# coreless.net
KiCad netlist of a schematic drawn in EAGLE
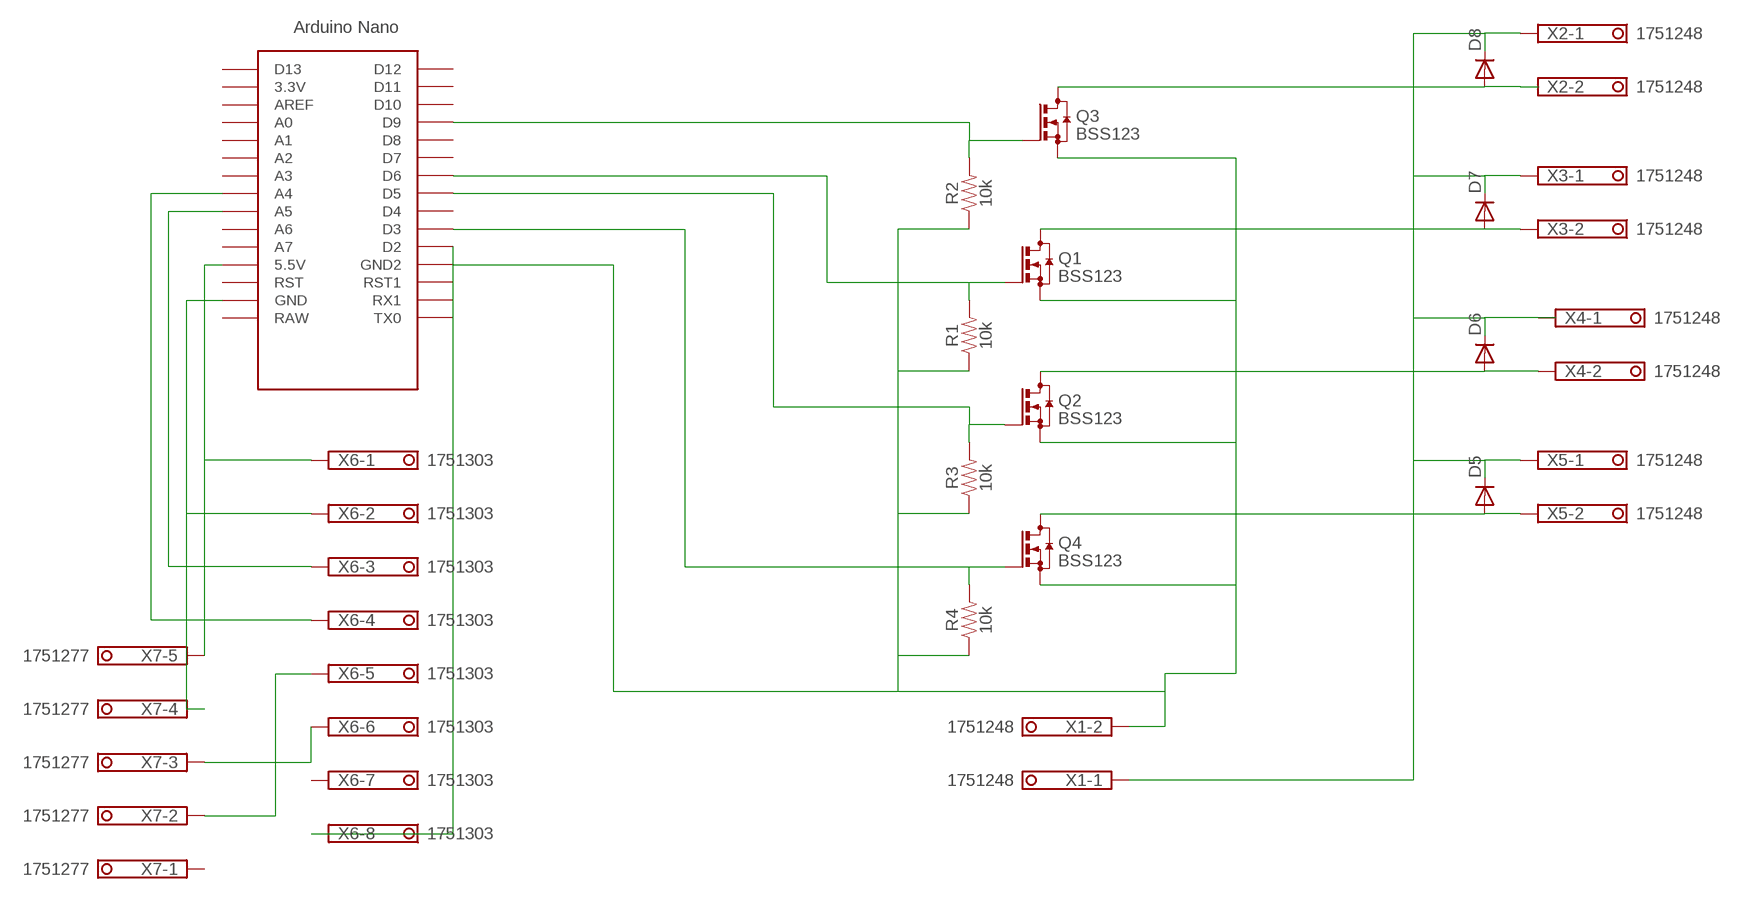
[diagram p0: schematic, sheet 1]

(export (version "E")
  (design (tool "Eeschema 10.0.6"))
  (components
    (comp (ref "D5")
      (value "DIODE-DO-214AC")
      (footprint "eagle-import:DO-214AC")
      (libsource (lib "eagle-import") (part "DIODE-DO-214AC"))
    )
    (comp (ref "D6")
      (value "DIODE-DO-214AC")
      (footprint "eagle-import:DO-214AC")
      (libsource (lib "eagle-import") (part "DIODE-DO-214AC"))
    )
    (comp (ref "D7")
      (value "DIODE-DO-214AC")
      (footprint "eagle-import:DO-214AC")
      (libsource (lib "eagle-import") (part "DIODE-DO-214AC"))
    )
    (comp (ref "D8")
      (value "DIODE-DO-214AC")
      (footprint "eagle-import:DO-214AC")
      (libsource (lib "eagle-import") (part "DIODE-DO-214AC"))
    )
    (comp (ref "Q1")
      (value "BSS123")
      (footprint "eagle-import:SOT23")
      (libsource (lib "eagle-import") (part "BSS123"))
    )
    (comp (ref "Q2")
      (value "BSS123")
      (footprint "eagle-import:SOT23")
      (libsource (lib "eagle-import") (part "BSS123"))
    )
    (comp (ref "Q3")
      (value "BSS123")
      (footprint "eagle-import:SOT23")
      (libsource (lib "eagle-import") (part "BSS123"))
    )
    (comp (ref "Q4")
      (value "BSS123")
      (footprint "eagle-import:SOT23")
      (libsource (lib "eagle-import") (part "BSS123"))
    )
    (comp (ref "R1")
      (value "10k")
      (footprint "eagle-import:0603")
      (libsource (lib "eagle-import") (part "10KOHM-0603-1/10W-1%"))
    )
    (comp (ref "R2")
      (value "10k")
      (footprint "eagle-import:0603")
      (libsource (lib "eagle-import") (part "10KOHM-0603-1/10W-1%"))
    )
    (comp (ref "R3")
      (value "10k")
      (footprint "eagle-import:0603")
      (libsource (lib "eagle-import") (part "10KOHM-0603-1/10W-1%"))
    )
    (comp (ref "R4")
      (value "10k")
      (footprint "eagle-import:0603")
      (libsource (lib "eagle-import") (part "10KOHM-0603-1/10W-1%"))
    )
    (comp (ref "U$1")
      (value "NANO")
      (footprint "eagle-import:NANO")
      (libsource (lib "eagle-import") (part "NANO"))
    )
    (comp (ref "X1")
      (value "1751248")
      (footprint "eagle-import:1751248")
      (libsource (lib "eagle-import") (part "1751248"))
    )
    (comp (ref "X2")
      (value "1751248")
      (footprint "eagle-import:1751248")
      (libsource (lib "eagle-import") (part "1751248"))
    )
    (comp (ref "X3")
      (value "1751248")
      (footprint "eagle-import:1751248")
      (libsource (lib "eagle-import") (part "1751248"))
    )
    (comp (ref "X4")
      (value "1751248")
      (footprint "eagle-import:1751248")
      (libsource (lib "eagle-import") (part "1751248"))
    )
    (comp (ref "X5")
      (value "1751248")
      (footprint "eagle-import:1751248")
      (libsource (lib "eagle-import") (part "1751248"))
    )
    (comp (ref "X6")
      (value "1751303")
      (footprint "eagle-import:1751303")
      (libsource (lib "eagle-import") (part "1751303"))
    )
    (comp (ref "X7")
      (value "1751277")
      (footprint "eagle-import:1751277")
      (libsource (lib "eagle-import") (part "1751277"))
    )
  )
  (nets
    (net (code "1") (name "Net-(Q1-D)") (class "Default")
      (node (ref "D7") (pin "A") (pinfunction "A_A") (pintype "passive"))
      (node (ref "Q1") (pin "3") (pinfunction "D_3") (pintype "passive"))
      (node (ref "X3") (pin "2") (pinfunction "K_2") (pintype "passive"))
    )
    (net (code "2") (name "Net-(Q1-G)") (class "Default")
      (node (ref "Q1") (pin "1") (pinfunction "G_1") (pintype "passive"))
      (node (ref "R1") (pin "2") (pinfunction "2_2") (pintype "passive"))
      (node (ref "U$1") (pin "D6") (pinfunction "D6_D6") (pintype "bidirectional"))
    )
    (net (code "3") (name "Net-(Q1-S)") (class "Default")
      (node (ref "Q1") (pin "2") (pinfunction "S_2") (pintype "passive"))
      (node (ref "Q2") (pin "2") (pinfunction "S_2") (pintype "passive"))
      (node (ref "Q3") (pin "2") (pinfunction "S_2") (pintype "passive"))
      (node (ref "Q4") (pin "2") (pinfunction "S_2") (pintype "passive"))
      (node (ref "R1") (pin "1") (pinfunction "1_1") (pintype "passive"))
      (node (ref "R2") (pin "1") (pinfunction "1_1") (pintype "passive"))
      (node (ref "R3") (pin "1") (pinfunction "1_1") (pintype "passive"))
      (node (ref "R4") (pin "1") (pinfunction "1_1") (pintype "passive"))
      (node (ref "U$1") (pin "GND1") (pinfunction "GND2_GND1") (pintype "bidirectional"))
      (node (ref "X1") (pin "2") (pinfunction "K_2") (pintype "passive"))
    )
    (net (code "4") (name "Net-(Q2-D)") (class "Default")
      (node (ref "D6") (pin "A") (pinfunction "A_A") (pintype "passive"))
      (node (ref "Q2") (pin "3") (pinfunction "D_3") (pintype "passive"))
      (node (ref "X4") (pin "2") (pinfunction "K_2") (pintype "passive"))
    )
    (net (code "5") (name "Net-(Q2-G)") (class "Default")
      (node (ref "Q2") (pin "1") (pinfunction "G_1") (pintype "passive"))
      (node (ref "R3") (pin "2") (pinfunction "2_2") (pintype "passive"))
      (node (ref "U$1") (pin "D5") (pinfunction "D5_D5") (pintype "bidirectional"))
    )
    (net (code "6") (name "Net-(Q3-D)") (class "Default")
      (node (ref "D8") (pin "A") (pinfunction "A_A") (pintype "passive"))
      (node (ref "Q3") (pin "3") (pinfunction "D_3") (pintype "passive"))
      (node (ref "X2") (pin "2") (pinfunction "K_2") (pintype "passive"))
    )
    (net (code "7") (name "Net-(Q3-G)") (class "Default")
      (node (ref "Q3") (pin "1") (pinfunction "G_1") (pintype "passive"))
      (node (ref "R2") (pin "2") (pinfunction "2_2") (pintype "passive"))
      (node (ref "U$1") (pin "D9") (pinfunction "D9_D9") (pintype "bidirectional"))
    )
    (net (code "8") (name "Net-(Q4-D)") (class "Default")
      (node (ref "D5") (pin "A") (pinfunction "A_A") (pintype "passive"))
      (node (ref "Q4") (pin "3") (pinfunction "D_3") (pintype "passive"))
      (node (ref "X5") (pin "2") (pinfunction "K_2") (pintype "passive"))
    )
    (net (code "9") (name "Net-(Q4-G)") (class "Default")
      (node (ref "Q4") (pin "1") (pinfunction "G_1") (pintype "passive"))
      (node (ref "R4") (pin "2") (pinfunction "2_2") (pintype "passive"))
      (node (ref "U$1") (pin "D3") (pinfunction "D3_D3") (pintype "bidirectional"))
    )
    (net (code "10") (name "Net-(U$1-5.5V)") (class "Default")
      (node (ref "U$1") (pin "5V") (pinfunction "5.5V_5V") (pintype "bidirectional"))
      (node (ref "X6") (pin "1") (pinfunction "K_1") (pintype "passive"))
      (node (ref "X7") (pin "5") (pinfunction "K_5") (pintype "passive"))
    )
    (net (code "11") (name "Net-(X1A-K)") (class "Default")
      (node (ref "D5") (pin "C") (pinfunction "C_C") (pintype "passive"))
      (node (ref "D6") (pin "C") (pinfunction "C_C") (pintype "passive"))
      (node (ref "D7") (pin "C") (pinfunction "C_C") (pintype "passive"))
      (node (ref "D8") (pin "C") (pinfunction "C_C") (pintype "passive"))
      (node (ref "X1") (pin "1") (pinfunction "K_1") (pintype "passive"))
      (node (ref "X2") (pin "1") (pinfunction "K_1") (pintype "passive"))
      (node (ref "X3") (pin "1") (pinfunction "K_1") (pintype "passive"))
      (node (ref "X4") (pin "1") (pinfunction "K_1") (pintype "passive"))
      (node (ref "X5") (pin "1") (pinfunction "K_1") (pintype "passive"))
    )
    (net (code "12") (name "Net-(X6B-K)") (class "Default")
      (node (ref "U$1") (pin "GND") (pinfunction "GND_GND") (pintype "bidirectional"))
      (node (ref "X6") (pin "2") (pinfunction "K_2") (pintype "passive"))
      (node (ref "X7") (pin "4") (pinfunction "K_4") (pintype "passive"))
    )
    (net (code "13") (name "Net-(X6C-K)") (class "Default")
      (node (ref "U$1") (pin "A5") (pinfunction "A5_A5") (pintype "bidirectional"))
      (node (ref "X6") (pin "3") (pinfunction "K_3") (pintype "passive"))
    )
    (net (code "14") (name "Net-(X6D-K)") (class "Default")
      (node (ref "U$1") (pin "A4") (pinfunction "A4_A4") (pintype "bidirectional"))
      (node (ref "X6") (pin "4") (pinfunction "K_4") (pintype "passive"))
    )
    (net (code "15") (name "Net-(X6E-K)") (class "Default")
      (node (ref "X6") (pin "5") (pinfunction "K_5") (pintype "passive"))
      (node (ref "X7") (pin "2") (pinfunction "K_2") (pintype "passive"))
    )
    (net (code "16") (name "Net-(X6F-K)") (class "Default")
      (node (ref "X6") (pin "6") (pinfunction "K_6") (pintype "passive"))
      (node (ref "X7") (pin "3") (pinfunction "K_3") (pintype "passive"))
    )
    (net (code "17") (name "Net-(X6H-K)") (class "Default")
      (node (ref "U$1") (pin "D2") (pinfunction "D2_D2") (pintype "bidirectional"))
      (node (ref "X6") (pin "8") (pinfunction "K_8") (pintype "passive"))
    )
    (net (code "18") (name "unconnected-(U$1-Pad3.3V)") (class "Default")
      (node (ref "U$1") (pin "3.3V") (pinfunction "3.3V_3.3V") (pintype "bidirectional"))
    )
    (net (code "19") (name "unconnected-(U$1-PadA0)") (class "Default")
      (node (ref "U$1") (pin "A0") (pinfunction "A0_A0") (pintype "bidirectional"))
    )
    (net (code "20") (name "unconnected-(U$1-PadA1)") (class "Default")
      (node (ref "U$1") (pin "A1") (pinfunction "A1_A1") (pintype "bidirectional"))
    )
    (net (code "21") (name "unconnected-(U$1-PadA2)") (class "Default")
      (node (ref "U$1") (pin "A2") (pinfunction "A2_A2") (pintype "bidirectional"))
    )
    (net (code "22") (name "unconnected-(U$1-PadA3)") (class "Default")
      (node (ref "U$1") (pin "A3") (pinfunction "A3_A3") (pintype "bidirectional"))
    )
    (net (code "23") (name "unconnected-(U$1-PadA6)") (class "Default")
      (node (ref "U$1") (pin "A6") (pinfunction "A6_A6") (pintype "bidirectional"))
    )
    (net (code "24") (name "unconnected-(U$1-PadA7)") (class "Default")
      (node (ref "U$1") (pin "A7") (pinfunction "A7_A7") (pintype "bidirectional"))
    )
    (net (code "25") (name "unconnected-(U$1-PadAREF)") (class "Default")
      (node (ref "U$1") (pin "AREF") (pinfunction "AREF_AREF") (pintype "bidirectional"))
    )
    (net (code "26") (name "unconnected-(U$1-PadD4)") (class "Default")
      (node (ref "U$1") (pin "D4") (pinfunction "D4_D4") (pintype "bidirectional"))
    )
    (net (code "27") (name "unconnected-(U$1-PadD7)") (class "Default")
      (node (ref "U$1") (pin "D7") (pinfunction "D7_D7") (pintype "bidirectional"))
    )
    (net (code "28") (name "unconnected-(U$1-PadD8)") (class "Default")
      (node (ref "U$1") (pin "D8") (pinfunction "D8_D8") (pintype "bidirectional"))
    )
    (net (code "29") (name "unconnected-(U$1-PadD10)") (class "Default")
      (node (ref "U$1") (pin "D10") (pinfunction "D10_D10") (pintype "bidirectional"))
    )
    (net (code "30") (name "unconnected-(U$1-PadD11)") (class "Default")
      (node (ref "U$1") (pin "D11") (pinfunction "D11_D11") (pintype "bidirectional"))
    )
    (net (code "31") (name "unconnected-(U$1-PadD12)") (class "Default")
      (node (ref "U$1") (pin "D12") (pinfunction "D12_D12") (pintype "bidirectional"))
    )
    (net (code "32") (name "unconnected-(U$1-PadD13)") (class "Default")
      (node (ref "U$1") (pin "D13") (pinfunction "D13_D13") (pintype "bidirectional"))
    )
    (net (code "33") (name "unconnected-(U$1-PadICSP1)") (class "Default")
      (node (ref "U$1") (pin "ICSP1") (pinfunction "ICSP1_ICSP1") (pintype "bidirectional"))
    )
    (net (code "34") (name "unconnected-(U$1-PadICSP2)") (class "Default")
      (node (ref "U$1") (pin "ICSP2") (pinfunction "ICSP2_ICSP2") (pintype "bidirectional"))
    )
    (net (code "35") (name "unconnected-(U$1-PadICSP3)") (class "Default")
      (node (ref "U$1") (pin "ICSP3") (pinfunction "ICSP3_ICSP3") (pintype "bidirectional"))
    )
    (net (code "36") (name "unconnected-(U$1-PadICSP4)") (class "Default")
      (node (ref "U$1") (pin "ICSP4") (pinfunction "ICSP4_ICSP4") (pintype "bidirectional"))
    )
    (net (code "37") (name "unconnected-(U$1-PadICSP5)") (class "Default")
      (node (ref "U$1") (pin "ICSP5") (pinfunction "ICSP5_ICSP5") (pintype "bidirectional"))
    )
    (net (code "38") (name "unconnected-(U$1-PadICSP6)") (class "Default")
      (node (ref "U$1") (pin "ICSP6") (pinfunction "ICSP6_ICSP6") (pintype "bidirectional"))
    )
    (net (code "39") (name "unconnected-(U$1-PadRAW)") (class "Default")
      (node (ref "U$1") (pin "RAW") (pinfunction "RAW_RAW") (pintype "bidirectional"))
    )
    (net (code "40") (name "unconnected-(U$1-PadRST)") (class "Default")
      (node (ref "U$1") (pin "RST") (pinfunction "RST_RST") (pintype "bidirectional"))
    )
    (net (code "41") (name "unconnected-(U$1-PadRST1)") (class "Default")
      (node (ref "U$1") (pin "RST1") (pinfunction "RST1_RST1") (pintype "bidirectional"))
    )
    (net (code "42") (name "unconnected-(U$1-PadRX1)") (class "Default")
      (node (ref "U$1") (pin "RX1") (pinfunction "RX1_RX1") (pintype "bidirectional"))
    )
    (net (code "43") (name "unconnected-(U$1-PadTX0)") (class "Default")
      (node (ref "U$1") (pin "TX0") (pinfunction "TX0_TX0") (pintype "bidirectional"))
    )
    (net (code "44") (name "unconnected-(X6G-K-Pad7)") (class "Default")
      (node (ref "X6") (pin "7") (pinfunction "K_7") (pintype "passive"))
    )
    (net (code "45") (name "unconnected-(X7A-K-Pad1)") (class "Default")
      (node (ref "X7") (pin "1") (pinfunction "K_1") (pintype "passive"))
    )
  )
)
